# ADC.net
KiCad netlist of a schematic drawn in Altium Designer
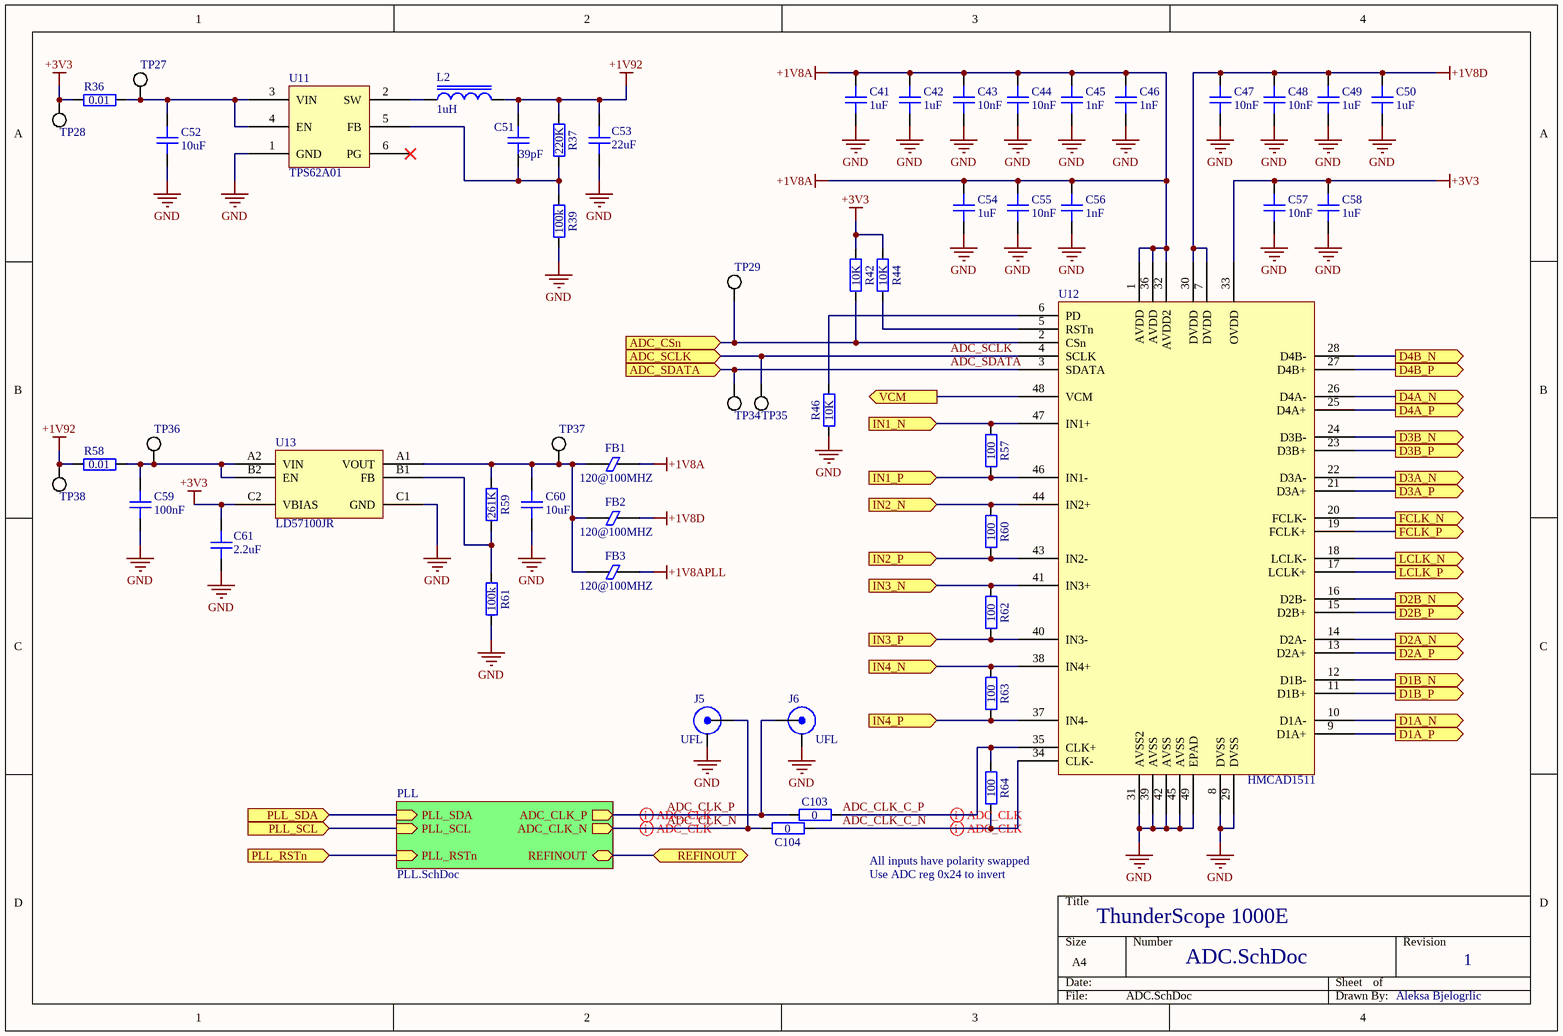
[diagram p0: ADC.SchDoc]

(export (version "E")
  (design (tool "Eeschema 10.0.6"))
  (components
    (comp (ref "C41")
      (value "1uF")
      (footprint "GEN_C_0402")
      (libsource (lib "DSO") (part "CAP 1uF 25V X5R 0402"))
    )
    (comp (ref "C42")
      (value "1uF")
      (footprint "GEN_C_0402")
      (libsource (lib "DSO") (part "CAP 1uF 25V X5R 0402"))
    )
    (comp (ref "C43")
      (value "10nF")
      (footprint "GEN_C_0402")
      (libsource (lib "DSO") (part "CAP 10nF 50V X7R 0402"))
    )
    (comp (ref "C44")
      (value "10nF")
      (footprint "GEN_C_0402")
      (libsource (lib "DSO") (part "CAP 10nF 50V X7R 0402"))
    )
    (comp (ref "C45")
      (value "1nF")
      (footprint "GEN_C_0402")
      (libsource (lib "DSO") (part "CAP 1nF 50V C0G 0402"))
    )
    (comp (ref "C46")
      (value "1nF")
      (footprint "GEN_C_0402")
      (libsource (lib "DSO") (part "CAP 1nF 50V C0G 0402"))
    )
    (comp (ref "C47")
      (value "10nF")
      (footprint "GEN_C_0402")
      (libsource (lib "DSO") (part "CAP 10nF 50V X7R 0402"))
    )
    (comp (ref "C48")
      (value "10nF")
      (footprint "GEN_C_0402")
      (libsource (lib "DSO") (part "CAP 10nF 50V X7R 0402"))
    )
    (comp (ref "C49")
      (value "1uF")
      (footprint "GEN_C_0402")
      (libsource (lib "DSO") (part "CAP 1uF 25V X5R 0402"))
    )
    (comp (ref "C50")
      (value "1uF")
      (footprint "GEN_C_0402")
      (libsource (lib "DSO") (part "CAP 1uF 25V X5R 0402"))
    )
    (comp (ref "C51")
      (value "39pF")
      (footprint "GEN_C_0402")
      (libsource (lib "DSO") (part "CAP 39pF 50V C0G 0402"))
    )
    (comp (ref "C52")
      (value "10uF")
      (footprint "GEN_C_0603")
      (libsource (lib "DSO") (part "CAP 10uF 10V X5R 0603"))
    )
    (comp (ref "C53")
      (value "22uF")
      (footprint "GEN_C_0805")
      (libsource (lib "DSO") (part "CAP 22uF 25V X5R 0805"))
    )
    (comp (ref "C54")
      (value "1uF")
      (footprint "GEN_C_0402")
      (libsource (lib "DSO") (part "CAP 1uF 25V X5R 0402"))
    )
    (comp (ref "C55")
      (value "10nF")
      (footprint "GEN_C_0402")
      (libsource (lib "DSO") (part "CAP 10nF 50V X7R 0402"))
    )
    (comp (ref "C56")
      (value "1nF")
      (footprint "GEN_C_0402")
      (libsource (lib "DSO") (part "CAP 1nF 50V C0G 0402"))
    )
    (comp (ref "C57")
      (value "10nF")
      (footprint "GEN_C_0402")
      (libsource (lib "DSO") (part "CAP 10nF 50V X7R 0402"))
    )
    (comp (ref "C58")
      (value "1uF")
      (footprint "GEN_C_0402")
      (libsource (lib "DSO") (part "CAP 1uF 25V X5R 0402"))
    )
    (comp (ref "C59")
      (value "100nF")
      (footprint "GEN_C_0402")
      (libsource (lib "DSO") (part "CAP 100nF 16V X7R 0402"))
    )
    (comp (ref "C60")
      (value "10uF")
      (footprint "GEN_C_0603")
      (libsource (lib "DSO") (part "CAP 10uF 10V X5R 0603"))
    )
    (comp (ref "C61")
      (value "2.2uF")
      (footprint "GEN_C_0402")
      (libsource (lib "DSO") (part "CAP 2.2uF 10V X5R 0402"))
    )
    (comp (ref "C103")
      (value "0")
      (footprint "GEN_R_0402")
      (fields
        (field (name "MANUFACTURER") "Yageo")
        (field (name "MANUFACTURER PART NUMBER") "RC0402JR-070RL")
      )
      (libsource (lib "DSO") (part "RES 0 OHM 1/16W 0402"))
    )
    (comp (ref "C104")
      (value "0")
      (footprint "GEN_R_0402")
      (fields
        (field (name "MANUFACTURER") "Yageo")
        (field (name "MANUFACTURER PART NUMBER") "RC0402JR-070RL")
      )
      (libsource (lib "DSO") (part "RES 0 OHM 1/16W 0402"))
    )
    (comp (ref "FB1")
      (value "120@100MHZ")
      (footprint "GEN_R_0402")
      (libsource (lib "DSO") (part "FERRITE BEAD 120 OHM 0402"))
    )
    (comp (ref "FB2")
      (value "120@100MHZ")
      (footprint "GEN_R_0402")
      (libsource (lib "DSO") (part "FERRITE BEAD 120 OHM 0402"))
    )
    (comp (ref "FB3")
      (value "120@100MHZ")
      (footprint "GEN_R_0402")
      (libsource (lib "DSO") (part "FERRITE BEAD 120 OHM 0402"))
    )
    (comp (ref "J5") (value "UFL") (footprint "TE_2334884-1") (libsource (lib "DSO") (part "UFL Jack SMD")))
    (comp (ref "J6") (value "UFL") (footprint "TE_2334884-1") (libsource (lib "DSO") (part "UFL Jack SMD")))
    (comp (ref "L2")
      (value "1uH")
      (footprint "GEN_L_1210")
      (libsource (lib "DSO") (part "IND 1uH 3.1A 45 MOHM 1210"))
    )
    (comp (ref "R36")
      (value "0.01")
      (footprint "GEN_R_0603")
      (fields (field (name "TOLERANCE") "1%"))
      (libsource (lib "DSO") (part "RES 0.01 OHM 1% 1/4W 0603"))
    )
    (comp (ref "R37")
      (value "220K")
      (footprint "GEN_R_0402")
      (fields (field (name "TOLERANCE") "1%"))
      (libsource (lib "DSO") (part "RES 220K OHM 1% 1/16W 0402"))
    )
    (comp (ref "R39")
      (value "100k")
      (footprint "GEN_R_0402")
      (fields (field (name "TOLERANCE") "1%"))
      (libsource (lib "DSO") (part "RES 100K OHM 1% 1/10W 0402"))
    )
    (comp (ref "R42")
      (value "10K")
      (footprint "GEN_R_0402")
      (fields (field (name "TOLERANCE") "1%"))
      (libsource (lib "DSO") (part "RES 10K OHM 1% 1/10W 0402"))
    )
    (comp (ref "R44")
      (value "10K")
      (footprint "GEN_R_0402")
      (fields (field (name "TOLERANCE") "1%"))
      (libsource (lib "DSO") (part "RES 10K OHM 1% 1/10W 0402"))
    )
    (comp (ref "R46")
      (value "10K")
      (footprint "GEN_R_0402")
      (fields (field (name "TOLERANCE") "1%"))
      (libsource (lib "") (part "RES 10K OHM 1% 1/10W 0402_1"))
    )
    (comp (ref "R57")
      (value "100")
      (footprint "GEN_R_0402")
      (fields (field (name "TOLERANCE") "1%"))
      (libsource (lib "DSO") (part "RES 100 OHM 1% 1/10W 0402"))
    )
    (comp (ref "R58")
      (value "0.01")
      (footprint "GEN_R_0603")
      (fields (field (name "TOLERANCE") "1%"))
      (libsource (lib "DSO") (part "RES 0.01 OHM 1% 1/4W 0603"))
    )
    (comp (ref "R59")
      (value "261K")
      (footprint "GEN_R_0402")
      (fields (field (name "TOLERANCE") "1%"))
      (libsource (lib "DSO") (part "RES 261K OHM 1% 1/16W 0402"))
    )
    (comp (ref "R60")
      (value "100")
      (footprint "GEN_R_0402")
      (fields (field (name "TOLERANCE") "1%"))
      (libsource (lib "DSO") (part "RES 100 OHM 1% 1/10W 0402"))
    )
    (comp (ref "R61")
      (value "100k")
      (footprint "GEN_R_0402")
      (fields (field (name "TOLERANCE") "1%"))
      (libsource (lib "DSO") (part "RES 100K OHM 1% 1/10W 0402"))
    )
    (comp (ref "R62")
      (value "100")
      (footprint "GEN_R_0402")
      (fields (field (name "TOLERANCE") "1%"))
      (libsource (lib "DSO") (part "RES 100 OHM 1% 1/10W 0402"))
    )
    (comp (ref "R63")
      (value "100")
      (footprint "GEN_R_0402")
      (fields (field (name "TOLERANCE") "1%"))
      (libsource (lib "DSO") (part "RES 100 OHM 1% 1/10W 0402"))
    )
    (comp (ref "R64")
      (value "100")
      (footprint "GEN_R_0402")
      (fields (field (name "TOLERANCE") "1%"))
      (libsource (lib "DSO") (part "RES 100 OHM 1% 1/10W 0402"))
    )
    (comp (ref "TP27") (value "PCB") (footprint "GEN_TP_PCB") (libsource (lib "DSO") (part "TP PCB 1mm")))
    (comp (ref "TP28") (value "PCB") (footprint "GEN_TP_PCB") (libsource (lib "DSO") (part "TP PCB 1mm")))
    (comp (ref "TP29") (value "PCB") (footprint "GEN_TP_PCB") (libsource (lib "DSO") (part "TP PCB 1mm")))
    (comp (ref "TP34") (value "PCB") (footprint "GEN_TP_PCB") (libsource (lib "DSO") (part "TP PCB 1mm")))
    (comp (ref "TP35") (value "PCB") (footprint "GEN_TP_PCB") (libsource (lib "DSO") (part "TP PCB 1mm")))
    (comp (ref "TP36") (value "PCB") (footprint "GEN_TP_PCB") (libsource (lib "DSO") (part "TP PCB 1mm")))
    (comp (ref "TP37") (value "PCB") (footprint "GEN_TP_PCB") (libsource (lib "DSO") (part "TP PCB 1mm")))
    (comp (ref "TP38") (value "PCB") (footprint "GEN_TP_PCB") (libsource (lib "DSO") (part "TP PCB 1mm")))
    (comp (ref "U11")
      (value "TPS62A01")
      (footprint "TI_SOT563_DRL0006A")
      (libsource (lib "DSO") (part "IC BUCK TPS62A01"))
    )
    (comp (ref "U12")
      (value "HMCAD1511")
      (footprint "AD_QFN48_LP7")
      (libsource (lib "DSO") (part "IC ADC HMCAD1511"))
    )
    (comp (ref "U13")
      (value "LD57100JR")
      (footprint "ST_FlipChip6")
      (libsource (lib "DSO") (part "IC LDO LD57100JR"))
    )
  )
  (nets
    (net (code "1") (name "+1V8A") (class "Default")
      (node (ref "C41") (pin "2") (pinfunction "2_2") (pintype "passive"))
      (node (ref "C42") (pin "2") (pinfunction "2_2") (pintype "passive"))
      (node (ref "C43") (pin "2") (pinfunction "2_2") (pintype "passive"))
      (node (ref "C44") (pin "2") (pinfunction "2_2") (pintype "passive"))
      (node (ref "C45") (pin "2") (pinfunction "2_2") (pintype "passive"))
      (node (ref "C46") (pin "2") (pinfunction "2_2") (pintype "passive"))
      (node (ref "C54") (pin "2") (pinfunction "2_2") (pintype "passive"))
      (node (ref "C55") (pin "2") (pinfunction "2_2") (pintype "passive"))
      (node (ref "C56") (pin "2") (pinfunction "2_2") (pintype "passive"))
      (node (ref "FB1") (pin "2") (pinfunction "2_2") (pintype "passive"))
      (node (ref "U12") (pin "1") (pinfunction "AVDD_1") (pintype "passive"))
      (node (ref "U12") (pin "32") (pinfunction "AVDD2_32") (pintype "passive"))
      (node (ref "U12") (pin "36") (pinfunction "AVDD_36") (pintype "passive"))
    )
    (net (code "2") (name "+1V8APLL") (class "Default")
      (node (ref "FB3") (pin "2") (pinfunction "2_2") (pintype "passive"))
    )
    (net (code "3") (name "+1V8D") (class "Default")
      (node (ref "C47") (pin "2") (pinfunction "2_2") (pintype "passive"))
      (node (ref "C48") (pin "2") (pinfunction "2_2") (pintype "passive"))
      (node (ref "C49") (pin "2") (pinfunction "2_2") (pintype "passive"))
      (node (ref "C50") (pin "2") (pinfunction "2_2") (pintype "passive"))
      (node (ref "FB2") (pin "2") (pinfunction "2_2") (pintype "passive"))
      (node (ref "U12") (pin "30") (pinfunction "DVDD_30") (pintype "passive"))
      (node (ref "U12") (pin "7") (pinfunction "DVDD_7") (pintype "passive"))
    )
    (net (code "4") (name "+1V92") (class "Default")
      (node (ref "C51") (pin "2") (pinfunction "2_2") (pintype "passive"))
      (node (ref "C53") (pin "2") (pinfunction "2_2") (pintype "passive"))
      (node (ref "L2") (pin "2") (pinfunction "2_2") (pintype "passive"))
      (node (ref "R37") (pin "2") (pinfunction "2_2") (pintype "passive"))
      (node (ref "R58") (pin "1") (pinfunction "1_1") (pintype "passive"))
      (node (ref "TP38") (pin "1") (pinfunction "1_1") (pintype "passive"))
    )
    (net (code "5") (name "+3V3") (class "Default")
      (node (ref "C57") (pin "2") (pinfunction "2_2") (pintype "passive"))
      (node (ref "C58") (pin "2") (pinfunction "2_2") (pintype "passive"))
      (node (ref "C61") (pin "2") (pinfunction "2_2") (pintype "passive"))
      (node (ref "R36") (pin "1") (pinfunction "1_1") (pintype "passive"))
      (node (ref "R42") (pin "2") (pinfunction "2_2") (pintype "passive"))
      (node (ref "R44") (pin "2") (pinfunction "2_2") (pintype "passive"))
      (node (ref "TP28") (pin "1") (pinfunction "1_1") (pintype "passive"))
      (node (ref "U12") (pin "33") (pinfunction "OVDD_33") (pintype "passive"))
      (node (ref "U13") (pin "C2") (pinfunction "VBIAS_C2") (pintype "passive"))
    )
    (net (code "6") (name "/ADC_CLK_C_N") (class "Default")
      (node (ref "C104") (pin "1") (pinfunction "1_1") (pintype "passive"))
      (node (ref "R64") (pin "1") (pinfunction "1_1") (pintype "passive"))
      (node (ref "U12") (pin "34") (pinfunction "CLK-_34") (pintype "passive"))
    )
    (net (code "7") (name "/ADC_CLK_C_P") (class "Default")
      (node (ref "C103") (pin "1") (pinfunction "1_1") (pintype "passive"))
      (node (ref "R64") (pin "2") (pinfunction "2_2") (pintype "passive"))
      (node (ref "U12") (pin "35") (pinfunction "CLK+_35") (pintype "passive"))
    )
    (net (code "8") (name "/ADC_CLK_N") (class "Default")
      (node (ref "C104") (pin "2") (pinfunction "2_2") (pintype "passive"))
      (node (ref "J5") (pin "1") (pinfunction "Signal_1") (pintype "passive"))
    )
    (net (code "9") (name "/ADC_CLK_P") (class "Default")
      (node (ref "C103") (pin "2") (pinfunction "2_2") (pintype "passive"))
      (node (ref "J6") (pin "1") (pinfunction "Signal_1") (pintype "passive"))
    )
    (net (code "10") (name "/ADC_CSn") (class "Default")
      (node (ref "R42") (pin "1") (pinfunction "1_1") (pintype "passive"))
      (node (ref "TP29") (pin "1") (pinfunction "1_1") (pintype "passive"))
      (node (ref "U12") (pin "2") (pinfunction "CSn_2") (pintype "passive"))
    )
    (net (code "11") (name "/ADC_SCLK") (class "Default")
      (node (ref "TP35") (pin "1") (pinfunction "1_1") (pintype "passive"))
      (node (ref "U12") (pin "4") (pinfunction "SCLK_4") (pintype "passive"))
    )
    (net (code "12") (name "/ADC_SDATA") (class "Default")
      (node (ref "TP34") (pin "1") (pinfunction "1_1") (pintype "passive"))
      (node (ref "U12") (pin "3") (pinfunction "SDATA_3") (pintype "passive"))
    )
    (net (code "13") (name "/D1A_N") (class "Default")
      (node (ref "U12") (pin "10") (pinfunction "D1A-_10") (pintype "passive"))
    )
    (net (code "14") (name "/D1A_P") (class "Default")
      (node (ref "U12") (pin "9") (pinfunction "D1A+_9") (pintype "passive"))
    )
    (net (code "15") (name "/D1B_N") (class "Default")
      (node (ref "U12") (pin "12") (pinfunction "D1B-_12") (pintype "passive"))
    )
    (net (code "16") (name "/D1B_P") (class "Default")
      (node (ref "U12") (pin "11") (pinfunction "D1B+_11") (pintype "passive"))
    )
    (net (code "17") (name "/D2A_N") (class "Default")
      (node (ref "U12") (pin "14") (pinfunction "D2A-_14") (pintype "passive"))
    )
    (net (code "18") (name "/D2A_P") (class "Default")
      (node (ref "U12") (pin "13") (pinfunction "D2A+_13") (pintype "passive"))
    )
    (net (code "19") (name "/D2B_N") (class "Default")
      (node (ref "U12") (pin "16") (pinfunction "D2B-_16") (pintype "passive"))
    )
    (net (code "20") (name "/D2B_P") (class "Default")
      (node (ref "U12") (pin "15") (pinfunction "D2B+_15") (pintype "passive"))
    )
    (net (code "21") (name "/D3A_N") (class "Default")
      (node (ref "U12") (pin "22") (pinfunction "D3A-_22") (pintype "passive"))
    )
    (net (code "22") (name "/D3A_P") (class "Default")
      (node (ref "U12") (pin "21") (pinfunction "D3A+_21") (pintype "passive"))
    )
    (net (code "23") (name "/D3B_N") (class "Default")
      (node (ref "U12") (pin "24") (pinfunction "D3B-_24") (pintype "passive"))
    )
    (net (code "24") (name "/D3B_P") (class "Default")
      (node (ref "U12") (pin "23") (pinfunction "D3B+_23") (pintype "passive"))
    )
    (net (code "25") (name "/D4A_N") (class "Default")
      (node (ref "U12") (pin "26") (pinfunction "D4A-_26") (pintype "passive"))
    )
    (net (code "26") (name "/D4A_P") (class "Default")
      (node (ref "U12") (pin "25") (pinfunction "D4A+_25") (pintype "passive"))
    )
    (net (code "27") (name "/D4B_N") (class "Default")
      (node (ref "U12") (pin "28") (pinfunction "D4B-_28") (pintype "passive"))
    )
    (net (code "28") (name "/D4B_P") (class "Default")
      (node (ref "U12") (pin "27") (pinfunction "D4B+_27") (pintype "passive"))
    )
    (net (code "29") (name "/FCLK_N") (class "Default")
      (node (ref "U12") (pin "20") (pinfunction "FCLK-_20") (pintype "passive"))
    )
    (net (code "30") (name "/FCLK_P") (class "Default")
      (node (ref "U12") (pin "19") (pinfunction "FCLK+_19") (pintype "passive"))
    )
    (net (code "31") (name "/IN1_N") (class "Default")
      (node (ref "R57") (pin "2") (pinfunction "2_2") (pintype "passive"))
      (node (ref "U12") (pin "47") (pinfunction "IN1+_47") (pintype "passive"))
    )
    (net (code "32") (name "/IN1_P") (class "Default")
      (node (ref "R57") (pin "1") (pinfunction "1_1") (pintype "passive"))
      (node (ref "U12") (pin "46") (pinfunction "IN1-_46") (pintype "passive"))
    )
    (net (code "33") (name "/IN2_N") (class "Default")
      (node (ref "R60") (pin "2") (pinfunction "2_2") (pintype "passive"))
      (node (ref "U12") (pin "44") (pinfunction "IN2+_44") (pintype "passive"))
    )
    (net (code "34") (name "/IN2_P") (class "Default")
      (node (ref "R60") (pin "1") (pinfunction "1_1") (pintype "passive"))
      (node (ref "U12") (pin "43") (pinfunction "IN2-_43") (pintype "passive"))
    )
    (net (code "35") (name "/IN3_N") (class "Default")
      (node (ref "R62") (pin "2") (pinfunction "2_2") (pintype "passive"))
      (node (ref "U12") (pin "41") (pinfunction "IN3+_41") (pintype "passive"))
    )
    (net (code "36") (name "/IN3_P") (class "Default")
      (node (ref "R62") (pin "1") (pinfunction "1_1") (pintype "passive"))
      (node (ref "U12") (pin "40") (pinfunction "IN3-_40") (pintype "passive"))
    )
    (net (code "37") (name "/IN4_N") (class "Default")
      (node (ref "R63") (pin "2") (pinfunction "2_2") (pintype "passive"))
      (node (ref "U12") (pin "38") (pinfunction "IN4+_38") (pintype "passive"))
    )
    (net (code "38") (name "/IN4_P") (class "Default")
      (node (ref "R63") (pin "1") (pinfunction "1_1") (pintype "passive"))
      (node (ref "U12") (pin "37") (pinfunction "IN4-_37") (pintype "passive"))
    )
    (net (code "39") (name "/LCLK_N") (class "Default")
      (node (ref "U12") (pin "18") (pinfunction "LCLK-_18") (pintype "passive"))
    )
    (net (code "40") (name "/LCLK_P") (class "Default")
      (node (ref "U12") (pin "17") (pinfunction "LCLK+_17") (pintype "passive"))
    )
    (net (code "45") (name "/VCM") (class "Default")
      (node (ref "U12") (pin "48") (pinfunction "VCM_48") (pintype "passive"))
    )
    (net (code "46") (name "GND") (class "Default")
      (node (ref "C41") (pin "1") (pinfunction "1_1") (pintype "passive"))
      (node (ref "C42") (pin "1") (pinfunction "1_1") (pintype "passive"))
      (node (ref "C43") (pin "1") (pinfunction "1_1") (pintype "passive"))
      (node (ref "C44") (pin "1") (pinfunction "1_1") (pintype "passive"))
      (node (ref "C45") (pin "1") (pinfunction "1_1") (pintype "passive"))
      (node (ref "C46") (pin "1") (pinfunction "1_1") (pintype "passive"))
      (node (ref "C47") (pin "1") (pinfunction "1_1") (pintype "passive"))
      (node (ref "C48") (pin "1") (pinfunction "1_1") (pintype "passive"))
      (node (ref "C49") (pin "1") (pinfunction "1_1") (pintype "passive"))
      (node (ref "C50") (pin "1") (pinfunction "1_1") (pintype "passive"))
      (node (ref "C52") (pin "1") (pinfunction "1_1") (pintype "passive"))
      (node (ref "C53") (pin "1") (pinfunction "1_1") (pintype "passive"))
      (node (ref "C54") (pin "1") (pinfunction "1_1") (pintype "passive"))
      (node (ref "C55") (pin "1") (pinfunction "1_1") (pintype "passive"))
      (node (ref "C56") (pin "1") (pinfunction "1_1") (pintype "passive"))
      (node (ref "C57") (pin "1") (pinfunction "1_1") (pintype "passive"))
      (node (ref "C58") (pin "1") (pinfunction "1_1") (pintype "passive"))
      (node (ref "C59") (pin "1") (pinfunction "1_1") (pintype "passive"))
      (node (ref "C60") (pin "1") (pinfunction "1_1") (pintype "passive"))
      (node (ref "C61") (pin "1") (pinfunction "1_1") (pintype "passive"))
      (node (ref "J5") (pin "2") (pinfunction "SHIELD_2") (pintype "passive"))
      (node (ref "J6") (pin "2") (pinfunction "SHIELD_2") (pintype "passive"))
      (node (ref "R39") (pin "1") (pinfunction "1_1") (pintype "passive"))
      (node (ref "R46") (pin "2") (pinfunction "2_2") (pintype "passive"))
      (node (ref "R61") (pin "1") (pinfunction "1_1") (pintype "passive"))
      (node (ref "U11") (pin "1") (pinfunction "GND_1") (pintype "power_in"))
      (node (ref "U12") (pin "29") (pinfunction "DVSS_29") (pintype "passive"))
      (node (ref "U12") (pin "31") (pinfunction "AVSS2_31") (pintype "passive"))
      (node (ref "U12") (pin "39") (pinfunction "AVSS_39") (pintype "passive"))
      (node (ref "U12") (pin "42") (pinfunction "AVSS_42") (pintype "passive"))
      (node (ref "U12") (pin "45") (pinfunction "AVSS_45") (pintype "passive"))
      (node (ref "U12") (pin "49") (pinfunction "EPAD_49") (pintype "passive"))
      (node (ref "U12") (pin "8") (pinfunction "DVSS_8") (pintype "passive"))
      (node (ref "U13") (pin "C1") (pinfunction "GND_C1") (pintype "passive"))
    )
    (net (code "47") (name "Net-(U11-EN)") (class "Default")
      (node (ref "C52") (pin "2") (pinfunction "2_2") (pintype "passive"))
      (node (ref "R36") (pin "2") (pinfunction "2_2") (pintype "passive"))
      (node (ref "TP27") (pin "1") (pinfunction "1_1") (pintype "passive"))
      (node (ref "U11") (pin "3") (pinfunction "VIN_3") (pintype "power_in"))
      (node (ref "U11") (pin "4") (pinfunction "EN_4") (pintype "passive"))
    )
    (net (code "48") (name "Net-(U11-FB)") (class "Default")
      (node (ref "C51") (pin "1") (pinfunction "1_1") (pintype "passive"))
      (node (ref "R37") (pin "1") (pinfunction "1_1") (pintype "passive"))
      (node (ref "R39") (pin "2") (pinfunction "2_2") (pintype "passive"))
      (node (ref "U11") (pin "5") (pinfunction "FB_5") (pintype "passive"))
    )
    (net (code "49") (name "Net-(U11-SW)") (class "Default")
      (node (ref "L2") (pin "1") (pinfunction "1_1") (pintype "passive"))
      (node (ref "U11") (pin "2") (pinfunction "SW_2") (pintype "passive"))
    )
    (net (code "50") (name "Net-(U12-PD)") (class "Default")
      (node (ref "R46") (pin "1") (pinfunction "1_1") (pintype "passive"))
      (node (ref "U12") (pin "6") (pinfunction "PD_6") (pintype "passive"))
    )
    (net (code "51") (name "Net-(U12-RSTn)") (class "Default")
      (node (ref "R44") (pin "1") (pinfunction "1_1") (pintype "passive"))
      (node (ref "U12") (pin "5") (pinfunction "RSTn_5") (pintype "passive"))
    )
    (net (code "52") (name "Net-(U13-EN)") (class "Default")
      (node (ref "C59") (pin "2") (pinfunction "2_2") (pintype "passive"))
      (node (ref "R58") (pin "2") (pinfunction "2_2") (pintype "passive"))
      (node (ref "TP36") (pin "1") (pinfunction "1_1") (pintype "passive"))
      (node (ref "U13") (pin "A2") (pinfunction "VIN_A2") (pintype "passive"))
      (node (ref "U13") (pin "B2") (pinfunction "EN_B2") (pintype "passive"))
    )
    (net (code "53") (name "Net-(U13-FB)") (class "Default")
      (node (ref "R59") (pin "1") (pinfunction "1_1") (pintype "passive"))
      (node (ref "R61") (pin "2") (pinfunction "2_2") (pintype "passive"))
      (node (ref "U13") (pin "B1") (pinfunction "FB_B1") (pintype "passive"))
    )
    (net (code "54") (name "Net-(U13-VOUT)") (class "Default")
      (node (ref "C60") (pin "2") (pinfunction "2_2") (pintype "passive"))
      (node (ref "FB1") (pin "1") (pinfunction "1_1") (pintype "passive"))
      (node (ref "FB2") (pin "1") (pinfunction "1_1") (pintype "passive"))
      (node (ref "FB3") (pin "1") (pinfunction "1_1") (pintype "passive"))
      (node (ref "R59") (pin "2") (pinfunction "2_2") (pintype "passive"))
      (node (ref "TP37") (pin "1") (pinfunction "1_1") (pintype "passive"))
      (node (ref "U13") (pin "A1") (pinfunction "VOUT_A1") (pintype "passive"))
    )
    (net (code "55") (name "unconnected-(U11-PG-Pad6)") (class "Default")
      (node (ref "U11") (pin "6") (pinfunction "PG_6") (pintype "passive+no_connect"))
    )
  )
)
